# design.net
KiCad netlist of a schematic drawn in Altium Designer
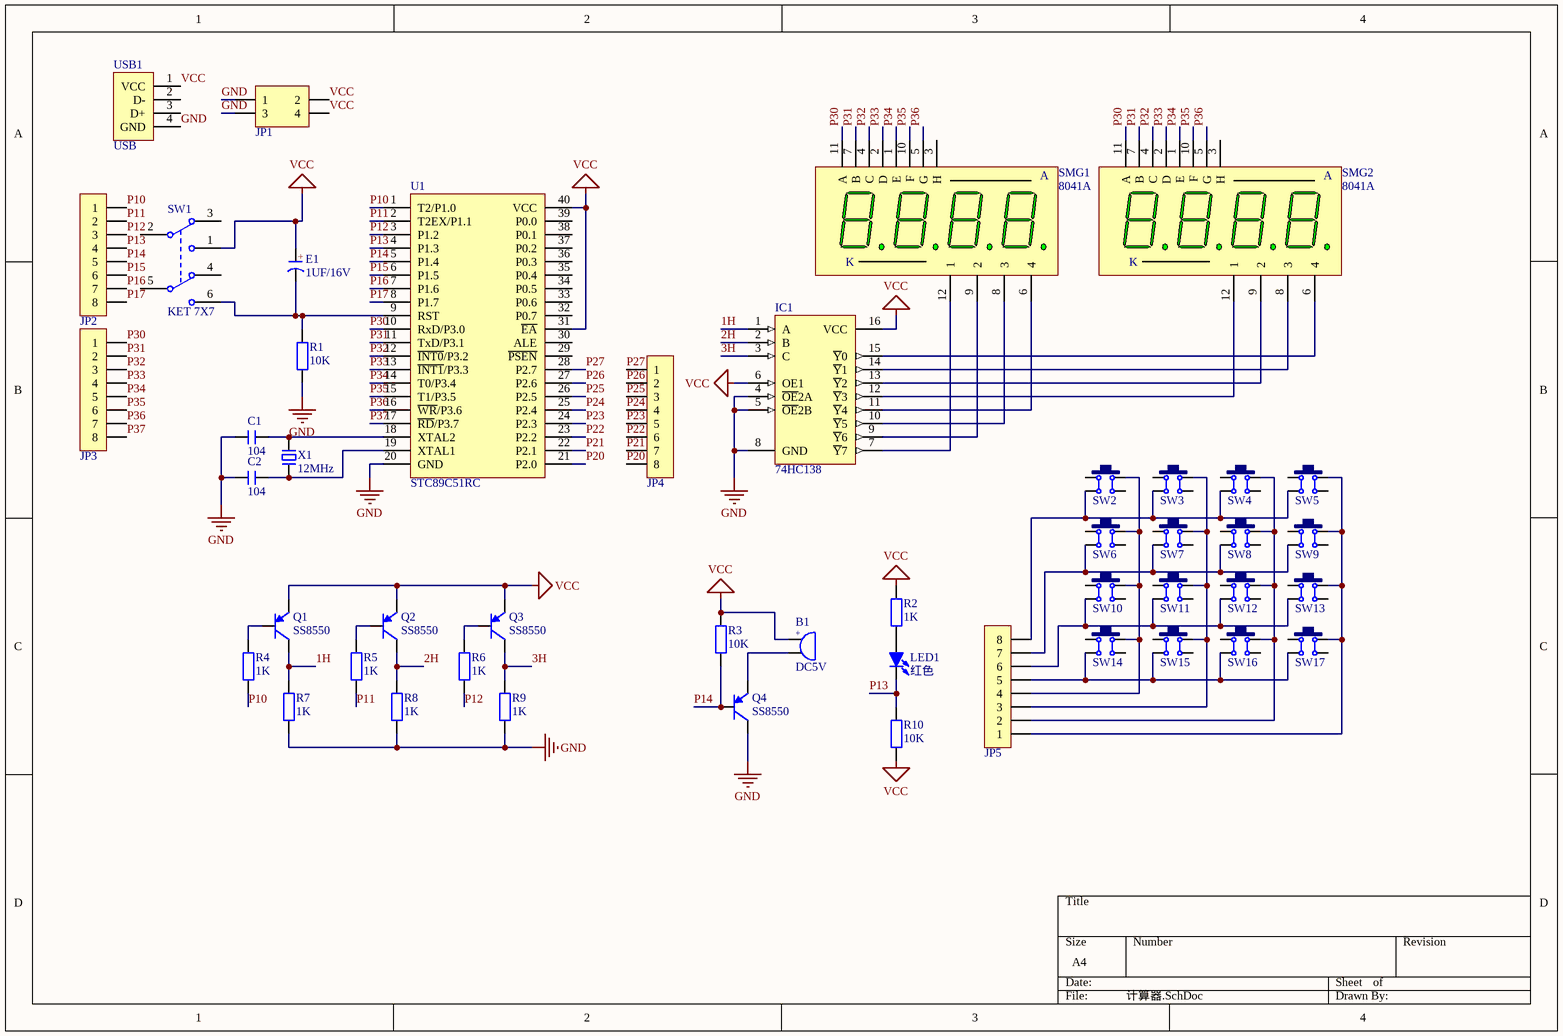
[diagram p0: 计算器.SchDoc]

(export (version "E")
  (design (tool "Eeschema 10.0.6"))
  (components
    (comp (ref "B1")
      (value "DC5V")
      (footprint "BEEP 5x9x5.5")
      (description "蜂鸣器")
      (fields (field (name "版权归属") "黎明电子style"))
      (libsource (lib "未分类器件") (part "BEEP"))
    )
    (comp (ref "C1")
      (value "104")
      (footprint "CC 1.8*3.6")
      (description "直插瓷片电容")
      (fields (field (name "版权归属") "黎明电子style"))
      (libsource (lib "电阻-电容-电感") (part "C-CC"))
    )
    (comp (ref "C2")
      (value "104")
      (footprint "CC 1.8*3.6")
      (description "直插瓷片电容")
      (fields (field (name "版权归属") "黎明电子style"))
      (libsource (lib "电阻-电容-电感") (part "C-CC"))
    )
    (comp (ref "E1")
      (value "1UF/16V")
      (footprint "CAP 1.5*4*8")
      (description "直插电解电容")
      (fields (field (name "版权归属") "黎明电子style"))
      (libsource (lib "电阻-电容-电感") (part "C-CAP"))
    )
    (comp (ref "IC1")
      (value "74HC138")
      (footprint "DIP16-300")
      (description "138译码器")
      (fields (field (name "版权归属") "黎明电子style"))
      (libsource (lib "74系列芯片") (part "74HC138"))
    )
    (comp (ref "JP1")
      (value "Header2X2")
      (footprint "HDR-2X2")
      (description "2*2P接插件")
      (fields (field (name "版权归属") "黎明电子style"))
      (libsource (lib "接插件") (part "Header 2X2"))
    )
    (comp (ref "JP2")
      (value "HDR-1X8")
      (footprint "HDR-1X8")
      (description "8P接插件")
      (fields (field (name "版权归属") "黎明电子style"))
      (libsource (lib "接插件") (part "Header 8"))
    )
    (comp (ref "JP3")
      (value "HDR-1X8")
      (footprint "HDR-1X8")
      (description "8P接插件")
      (fields (field (name "版权归属") "黎明电子style"))
      (libsource (lib "接插件") (part "Header 8"))
    )
    (comp (ref "JP4")
      (value "HDR-1X8")
      (footprint "HDR-1X8")
      (description "8P接插件")
      (fields (field (name "版权归属") "黎明电子style"))
      (libsource (lib "") (part "Header 8_1"))
    )
    (comp (ref "JP5")
      (value "HDR-1X8")
      (footprint "HDR-1X8")
      (description "8P接插件")
      (fields (field (name "版权归属") "黎明电子style"))
      (libsource (lib "") (part "Header 8_2"))
    )
    (comp (ref "LED1")
      (value "红色")
      (footprint "LED 5MM-B")
      (description "5mm插件LED")
      (fields (field (name "版权归属") "黎明电子style"))
      (libsource (lib "LED") (part "LED-5MM"))
    )
    (comp (ref "Q1")
      (value "SS8550")
      (footprint "TO92A")
      (description "高频放大-PNP型")
      (fields (field (name "版权归属") "黎明电子style"))
      (libsource (lib "三极管") (part "8550-DIP"))
    )
    (comp (ref "Q2")
      (value "SS8550")
      (footprint "TO92A")
      (description "高频放大-PNP型")
      (fields (field (name "版权归属") "黎明电子style"))
      (libsource (lib "三极管") (part "8550-DIP"))
    )
    (comp (ref "Q3")
      (value "SS8550")
      (footprint "TO92A")
      (description "高频放大-PNP型")
      (fields (field (name "版权归属") "黎明电子style"))
      (libsource (lib "三极管") (part "8550-DIP"))
    )
    (comp (ref "Q4")
      (value "SS8550")
      (footprint "TO92A")
      (description "高频放大-PNP型")
      (fields (field (name "版权归属") "黎明电子style"))
      (libsource (lib "三极管") (part "8550-DIP"))
    )
    (comp (ref "R1")
      (value "10K")
      (footprint "RS 1/4W")
      (description "直插色环电阻")
      (fields (field (name "版权归属") "黎明电子style"))
      (libsource (lib "电阻-电容-电感") (part "R-CRR"))
    )
    (comp (ref "R2")
      (value "1K")
      (footprint "RS 1/4W")
      (description "直插色环电阻")
      (fields (field (name "版权归属") "黎明电子style"))
      (libsource (lib "电阻-电容-电感") (part "R-CRR"))
    )
    (comp (ref "R3")
      (value "10K")
      (footprint "RS 1/4W")
      (description "直插色环电阻")
      (fields (field (name "版权归属") "黎明电子style"))
      (libsource (lib "电阻-电容-电感") (part "R-CRR"))
    )
    (comp (ref "R4")
      (value "1K")
      (footprint "RS 1/4W")
      (description "直插色环电阻")
      (fields (field (name "版权归属") "黎明电子style"))
      (libsource (lib "电阻-电容-电感") (part "R-CRR"))
    )
    (comp (ref "R5")
      (value "1K")
      (footprint "RS 1/4W")
      (description "直插色环电阻")
      (fields (field (name "版权归属") "黎明电子style"))
      (libsource (lib "电阻-电容-电感") (part "R-CRR"))
    )
    (comp (ref "R6")
      (value "1K")
      (footprint "RS 1/4W")
      (description "直插色环电阻")
      (fields (field (name "版权归属") "黎明电子style"))
      (libsource (lib "电阻-电容-电感") (part "R-CRR"))
    )
    (comp (ref "R7")
      (value "1K")
      (footprint "RS 1/4W")
      (description "直插色环电阻")
      (fields (field (name "版权归属") "黎明电子style"))
      (libsource (lib "电阻-电容-电感") (part "R-CRR"))
    )
    (comp (ref "R8")
      (value "1K")
      (footprint "RS 1/4W")
      (description "直插色环电阻")
      (fields (field (name "版权归属") "黎明电子style"))
      (libsource (lib "电阻-电容-电感") (part "R-CRR"))
    )
    (comp (ref "R9")
      (value "1K")
      (footprint "RS 1/4W")
      (description "直插色环电阻")
      (fields (field (name "版权归属") "黎明电子style"))
      (libsource (lib "电阻-电容-电感") (part "R-CRR"))
    )
    (comp (ref "R10")
      (value "10K")
      (footprint "RS 1/4W")
      (description "直插色环电阻")
      (fields (field (name "版权归属") "黎明电子style"))
      (libsource (lib "电阻-电容-电感") (part "R-CRR"))
    )
    (comp (ref "SMG1")
      (value "8041A")
      (footprint "SMG 0.8-4P")
      (description "0.8寸4位共阴数码管")
      (fields (field (name "版权归属") "黎明电子style"))
      (libsource (lib "显示器件") (part "8041A"))
    )
    (comp (ref "SMG2")
      (value "8041A")
      (footprint "SMG 0.8-4P")
      (description "0.8寸4位共阴数码管")
      (fields (field (name "版权归属") "黎明电子style"))
      (libsource (lib "显示器件") (part "8041A"))
    )
    (comp (ref "SW1")
      (value "KET 7X7")
      (footprint "KFT DIP-7X7")
      (description "7*7自锁开关")
      (fields (field (name "版权归属") "黎明电子style"))
      (libsource (lib "按键-开关") (part "KET 7X7"))
    )
    (comp (ref "SW2")
      (value "6x6x5")
      (footprint "TSW DIP-6*6*6")
      (description "直插6x6轻触开关")
      (fields (field (name "版权归属") "黎明电子style"))
      (libsource (lib "按键-开关") (part "TSW DIP-6x6"))
    )
    (comp (ref "SW3")
      (value "6x6x5")
      (footprint "TSW DIP-6*6*6")
      (description "直插6x6轻触开关")
      (fields (field (name "版权归属") "黎明电子style"))
      (libsource (lib "按键-开关") (part "TSW DIP-6x6"))
    )
    (comp (ref "SW4")
      (value "6x6x5")
      (footprint "TSW DIP-6*6*6")
      (description "直插6x6轻触开关")
      (fields (field (name "版权归属") "黎明电子style"))
      (libsource (lib "按键-开关") (part "TSW DIP-6x6"))
    )
    (comp (ref "SW5")
      (value "6x6x5")
      (footprint "TSW DIP-6*6*6")
      (description "直插6x6轻触开关")
      (fields (field (name "版权归属") "黎明电子style"))
      (libsource (lib "按键-开关") (part "TSW DIP-6x6"))
    )
    (comp (ref "SW6")
      (value "6x6x5")
      (footprint "TSW DIP-6*6*6")
      (description "直插6x6轻触开关")
      (fields (field (name "版权归属") "黎明电子style"))
      (libsource (lib "按键-开关") (part "TSW DIP-6x6"))
    )
    (comp (ref "SW7")
      (value "6x6x5")
      (footprint "TSW DIP-6*6*6")
      (description "直插6x6轻触开关")
      (fields (field (name "版权归属") "黎明电子style"))
      (libsource (lib "按键-开关") (part "TSW DIP-6x6"))
    )
    (comp (ref "SW8")
      (value "6x6x5")
      (footprint "TSW DIP-6*6*6")
      (description "直插6x6轻触开关")
      (fields (field (name "版权归属") "黎明电子style"))
      (libsource (lib "按键-开关") (part "TSW DIP-6x6"))
    )
    (comp (ref "SW9")
      (value "6x6x5")
      (footprint "TSW DIP-6*6*6")
      (description "直插6x6轻触开关")
      (fields (field (name "版权归属") "黎明电子style"))
      (libsource (lib "按键-开关") (part "TSW DIP-6x6"))
    )
    (comp (ref "SW10")
      (value "6x6x5")
      (footprint "TSW DIP-6*6*6")
      (description "直插6x6轻触开关")
      (fields (field (name "版权归属") "黎明电子style"))
      (libsource (lib "按键-开关") (part "TSW DIP-6x6"))
    )
    (comp (ref "SW11")
      (value "6x6x5")
      (footprint "TSW DIP-6*6*6")
      (description "直插6x6轻触开关")
      (fields (field (name "版权归属") "黎明电子style"))
      (libsource (lib "按键-开关") (part "TSW DIP-6x6"))
    )
    (comp (ref "SW12")
      (value "6x6x5")
      (footprint "TSW DIP-6*6*6")
      (description "直插6x6轻触开关")
      (fields (field (name "版权归属") "黎明电子style"))
      (libsource (lib "按键-开关") (part "TSW DIP-6x6"))
    )
    (comp (ref "SW13")
      (value "6x6x5")
      (footprint "TSW DIP-6*6*6")
      (description "直插6x6轻触开关")
      (fields (field (name "版权归属") "黎明电子style"))
      (libsource (lib "按键-开关") (part "TSW DIP-6x6"))
    )
    (comp (ref "SW14")
      (value "6x6x5")
      (footprint "TSW DIP-6*6*6")
      (description "直插6x6轻触开关")
      (fields (field (name "版权归属") "黎明电子style"))
      (libsource (lib "按键-开关") (part "TSW DIP-6x6"))
    )
    (comp (ref "SW15")
      (value "6x6x5")
      (footprint "TSW DIP-6*6*6")
      (description "直插6x6轻触开关")
      (fields (field (name "版权归属") "黎明电子style"))
      (libsource (lib "按键-开关") (part "TSW DIP-6x6"))
    )
    (comp (ref "SW16")
      (value "6x6x5")
      (footprint "TSW DIP-6*6*6")
      (description "直插6x6轻触开关")
      (fields (field (name "版权归属") "黎明电子style"))
      (libsource (lib "按键-开关") (part "TSW DIP-6x6"))
    )
    (comp (ref "SW17")
      (value "6x6x5")
      (footprint "TSW DIP-6*6*6")
      (description "直插6x6轻触开关")
      (fields (field (name "版权归属") "黎明电子style"))
      (libsource (lib "按键-开关") (part "TSW DIP-6x6"))
    )
    (comp (ref "U1")
      (value "STC89C51RC")
      (footprint "DIP40-600")
      (description "STC单片机")
      (fields (field (name "版权归属") "黎明电子style"))
      (libsource (lib "STC系列单片机") (part "STC89C51RC"))
    )
    (comp (ref "USB1")
      (value "USB")
      (footprint "USB-A/S_A")
      (description "USB-A型母接口")
      (fields (field (name "版权归属") "黎明电子style"))
      (libsource (lib "接口类") (part "USB-A/S"))
    )
    (comp (ref "X1")
      (value "12MHz")
      (footprint "XTAL-3X10")
      (description "2脚晶振")
      (fields (field (name "版权归属") "黎明电子style"))
      (libsource (lib "保险丝-晶振") (part "XTAL-2"))
    )
  )
  (nets
    (net (code "1") (name "/1H") (class "Default")
      (node (ref "IC1") (pin "1") (pinfunction "A_1") (pintype "input"))
      (node (ref "Q1") (pin "3") (pinfunction "C_3") (pintype "passive"))
      (node (ref "R7") (pin "2") (pinfunction "2_2") (pintype "passive"))
    )
    (net (code "2") (name "/2H") (class "Default")
      (node (ref "IC1") (pin "2") (pinfunction "B_2") (pintype "input"))
      (node (ref "Q2") (pin "3") (pinfunction "C_3") (pintype "passive"))
      (node (ref "R8") (pin "2") (pinfunction "2_2") (pintype "passive"))
    )
    (net (code "3") (name "/3H") (class "Default")
      (node (ref "IC1") (pin "3") (pinfunction "C_3") (pintype "input"))
      (node (ref "Q3") (pin "3") (pinfunction "C_3") (pintype "passive"))
      (node (ref "R9") (pin "2") (pinfunction "2_2") (pintype "passive"))
    )
    (net (code "4") (name "/P10") (class "Default")
      (node (ref "JP2") (pin "1") (pinfunction "1_1") (pintype "passive"))
      (node (ref "R4") (pin "1") (pinfunction "1_1") (pintype "passive"))
      (node (ref "U1") (pin "1") (pinfunction "T2/P1.0_1") (pintype "passive"))
    )
    (net (code "5") (name "/P11") (class "Default")
      (node (ref "JP2") (pin "2") (pinfunction "2_2") (pintype "passive"))
      (node (ref "R5") (pin "1") (pinfunction "1_1") (pintype "passive"))
      (node (ref "U1") (pin "2") (pinfunction "T2EX/P1.1_2") (pintype "passive"))
    )
    (net (code "6") (name "/P12") (class "Default")
      (node (ref "JP2") (pin "3") (pinfunction "3_3") (pintype "passive"))
      (node (ref "R6") (pin "1") (pinfunction "1_1") (pintype "passive"))
      (node (ref "U1") (pin "3") (pinfunction "P1.2_3") (pintype "passive"))
    )
    (net (code "7") (name "/P13") (class "Default")
      (node (ref "JP2") (pin "4") (pinfunction "4_4") (pintype "passive"))
      (node (ref "LED1") (pin "2") (pinfunction "K_2") (pintype "passive"))
      (node (ref "R10") (pin "2") (pinfunction "2_2") (pintype "passive"))
      (node (ref "U1") (pin "4") (pinfunction "P1.3_4") (pintype "passive"))
    )
    (net (code "8") (name "/P14") (class "Default")
      (node (ref "JP2") (pin "5") (pinfunction "5_5") (pintype "passive"))
      (node (ref "Q4") (pin "2") (pinfunction "B_2") (pintype "passive"))
      (node (ref "R3") (pin "1") (pinfunction "1_1") (pintype "passive"))
      (node (ref "U1") (pin "5") (pinfunction "P1.4_5") (pintype "passive"))
    )
    (net (code "9") (name "/P15") (class "Default")
      (node (ref "JP2") (pin "6") (pinfunction "6_6") (pintype "passive"))
      (node (ref "U1") (pin "6") (pinfunction "P1.5_6") (pintype "passive"))
    )
    (net (code "10") (name "/P16") (class "Default")
      (node (ref "JP2") (pin "7") (pinfunction "7_7") (pintype "passive"))
      (node (ref "U1") (pin "7") (pinfunction "P1.6_7") (pintype "passive"))
    )
    (net (code "11") (name "/P17") (class "Default")
      (node (ref "JP2") (pin "8") (pinfunction "8_8") (pintype "passive"))
      (node (ref "U1") (pin "8") (pinfunction "P1.7_8") (pintype "passive"))
    )
    (net (code "12") (name "/P20") (class "Default")
      (node (ref "JP4") (pin "8") (pinfunction "8_8") (pintype "passive"))
      (node (ref "U1") (pin "21") (pinfunction "P2.0_21") (pintype "passive"))
    )
    (net (code "13") (name "/P21") (class "Default")
      (node (ref "JP4") (pin "7") (pinfunction "7_7") (pintype "passive"))
      (node (ref "U1") (pin "22") (pinfunction "P2.1_22") (pintype "passive"))
    )
    (net (code "14") (name "/P22") (class "Default")
      (node (ref "JP4") (pin "6") (pinfunction "6_6") (pintype "passive"))
      (node (ref "U1") (pin "23") (pinfunction "P2.2_23") (pintype "passive"))
    )
    (net (code "15") (name "/P23") (class "Default")
      (node (ref "JP4") (pin "5") (pinfunction "5_5") (pintype "passive"))
      (node (ref "U1") (pin "24") (pinfunction "P2.3_24") (pintype "passive"))
    )
    (net (code "16") (name "/P24") (class "Default")
      (node (ref "JP4") (pin "4") (pinfunction "4_4") (pintype "passive"))
      (node (ref "U1") (pin "25") (pinfunction "P2.4_25") (pintype "passive"))
    )
    (net (code "17") (name "/P25") (class "Default")
      (node (ref "JP4") (pin "3") (pinfunction "3_3") (pintype "passive"))
      (node (ref "U1") (pin "26") (pinfunction "P2.5_26") (pintype "passive"))
    )
    (net (code "18") (name "/P26") (class "Default")
      (node (ref "JP4") (pin "2") (pinfunction "2_2") (pintype "passive"))
      (node (ref "U1") (pin "27") (pinfunction "P2.6_27") (pintype "passive"))
    )
    (net (code "19") (name "/P27") (class "Default")
      (node (ref "JP4") (pin "1") (pinfunction "1_1") (pintype "passive"))
      (node (ref "U1") (pin "28") (pinfunction "P2.7_28") (pintype "passive"))
    )
    (net (code "20") (name "/P30") (class "Default")
      (node (ref "JP3") (pin "1") (pinfunction "1_1") (pintype "passive"))
      (node (ref "SMG1") (pin "11") (pinfunction "A_11") (pintype "passive"))
      (node (ref "SMG2") (pin "11") (pinfunction "A_11") (pintype "passive"))
      (node (ref "U1") (pin "10") (pinfunction "RxD/P3.0_10") (pintype "passive"))
    )
    (net (code "21") (name "/P31") (class "Default")
      (node (ref "JP3") (pin "2") (pinfunction "2_2") (pintype "passive"))
      (node (ref "SMG1") (pin "7") (pinfunction "B_7") (pintype "passive"))
      (node (ref "SMG2") (pin "7") (pinfunction "B_7") (pintype "passive"))
      (node (ref "U1") (pin "11") (pinfunction "TxD/P3.1_11") (pintype "passive"))
    )
    (net (code "22") (name "/P32") (class "Default")
      (node (ref "JP3") (pin "3") (pinfunction "3_3") (pintype "passive"))
      (node (ref "SMG1") (pin "4") (pinfunction "C_4") (pintype "passive"))
      (node (ref "SMG2") (pin "4") (pinfunction "C_4") (pintype "passive"))
      (node (ref "U1") (pin "12") (pinfunction "~{INT0}/P3.2_12") (pintype "passive"))
    )
    (net (code "23") (name "/P33") (class "Default")
      (node (ref "JP3") (pin "4") (pinfunction "4_4") (pintype "passive"))
      (node (ref "SMG1") (pin "2") (pinfunction "D_2") (pintype "passive"))
      (node (ref "SMG2") (pin "2") (pinfunction "D_2") (pintype "passive"))
      (node (ref "U1") (pin "13") (pinfunction "~{INT1}/P3.3_13") (pintype "passive"))
    )
    (net (code "24") (name "/P34") (class "Default")
      (node (ref "JP3") (pin "5") (pinfunction "5_5") (pintype "passive"))
      (node (ref "SMG1") (pin "1") (pinfunction "E_1") (pintype "passive"))
      (node (ref "SMG2") (pin "1") (pinfunction "E_1") (pintype "passive"))
      (node (ref "U1") (pin "14") (pinfunction "T0/P3.4_14") (pintype "passive"))
    )
    (net (code "25") (name "/P35") (class "Default")
      (node (ref "JP3") (pin "6") (pinfunction "6_6") (pintype "passive"))
      (node (ref "SMG1") (pin "10") (pinfunction "F_10") (pintype "passive"))
      (node (ref "SMG2") (pin "10") (pinfunction "F_10") (pintype "passive"))
      (node (ref "U1") (pin "15") (pinfunction "T1/P3.5_15") (pintype "passive"))
    )
    (net (code "26") (name "/P36") (class "Default")
      (node (ref "JP3") (pin "7") (pinfunction "7_7") (pintype "passive"))
      (node (ref "SMG1") (pin "5") (pinfunction "G_5") (pintype "passive"))
      (node (ref "SMG2") (pin "5") (pinfunction "G_5") (pintype "passive"))
      (node (ref "U1") (pin "16") (pinfunction "~{WR}/P3.6_16") (pintype "passive"))
    )
    (net (code "27") (name "/P37") (class "Default")
      (node (ref "JP3") (pin "8") (pinfunction "8_8") (pintype "passive"))
      (node (ref "U1") (pin "17") (pinfunction "~{RD}/P3.7_17") (pintype "passive"))
    )
    (net (code "28") (name "GND") (class "Default")
      (node (ref "C1") (pin "1") (pinfunction "1_1") (pintype "passive"))
      (node (ref "C2") (pin "1") (pinfunction "1_1") (pintype "passive"))
      (node (ref "IC1") (pin "4") (pinfunction "~{OE}2A_4") (pintype "input"))
      (node (ref "IC1") (pin "5") (pinfunction "~{OE}2B_5") (pintype "input"))
      (node (ref "IC1") (pin "8") (pinfunction "GND_8") (pintype "power_in"))
      (node (ref "JP1") (pin "1") (pinfunction "1_1") (pintype "passive"))
      (node (ref "JP1") (pin "3") (pinfunction "3_3") (pintype "passive"))
      (node (ref "Q4") (pin "3") (pinfunction "C_3") (pintype "passive"))
      (node (ref "R1") (pin "1") (pinfunction "1_1") (pintype "passive"))
      (node (ref "R7") (pin "1") (pinfunction "1_1") (pintype "passive"))
      (node (ref "R8") (pin "1") (pinfunction "1_1") (pintype "passive"))
      (node (ref "R9") (pin "1") (pinfunction "1_1") (pintype "passive"))
      (node (ref "U1") (pin "20") (pinfunction "GND_20") (pintype "passive"))
      (node (ref "USB1") (pin "4") (pinfunction "GND_4") (pintype "passive"))
    )
    (net (code "29") (name "Net-(E1-K)") (class "Default")
      (node (ref "E1") (pin "2") (pinfunction "K_2") (pintype "passive"))
      (node (ref "R1") (pin "2") (pinfunction "2_2") (pintype "passive"))
      (node (ref "SW1") (pin "6") (pinfunction "NC2_6") (pintype "passive"))
      (node (ref "U1") (pin "9") (pinfunction "RST_9") (pintype "passive"))
    )
    (net (code "30") (name "Net-(IC1-~{Y}0)") (class "Default")
      (node (ref "IC1") (pin "15") (pinfunction "~{Y}0_15") (pintype "output"))
      (node (ref "SMG2") (pin "6") (pinfunction "4_6") (pintype "passive"))
    )
    (net (code "31") (name "Net-(IC1-~{Y}1)") (class "Default")
      (node (ref "IC1") (pin "14") (pinfunction "~{Y}1_14") (pintype "output"))
      (node (ref "SMG2") (pin "8") (pinfunction "3_8") (pintype "passive"))
    )
    (net (code "32") (name "Net-(IC1-~{Y}2)") (class "Default")
      (node (ref "IC1") (pin "13") (pinfunction "~{Y}2_13") (pintype "output"))
      (node (ref "SMG2") (pin "9") (pinfunction "2_9") (pintype "passive"))
    )
    (net (code "33") (name "Net-(IC1-~{Y}3)") (class "Default")
      (node (ref "IC1") (pin "12") (pinfunction "~{Y}3_12") (pintype "output"))
      (node (ref "SMG2") (pin "12") (pinfunction "1_12") (pintype "passive"))
    )
    (net (code "34") (name "Net-(IC1-~{Y}4)") (class "Default")
      (node (ref "IC1") (pin "11") (pinfunction "~{Y}4_11") (pintype "output"))
      (node (ref "SMG1") (pin "6") (pinfunction "4_6") (pintype "passive"))
    )
    (net (code "35") (name "Net-(IC1-~{Y}5)") (class "Default")
      (node (ref "IC1") (pin "10") (pinfunction "~{Y}5_10") (pintype "output"))
      (node (ref "SMG1") (pin "8") (pinfunction "3_8") (pintype "passive"))
    )
    (net (code "36") (name "Net-(IC1-~{Y}6)") (class "Default")
      (node (ref "IC1") (pin "9") (pinfunction "~{Y}6_9") (pintype "output"))
      (node (ref "SMG1") (pin "9") (pinfunction "2_9") (pintype "passive"))
    )
    (net (code "37") (name "Net-(IC1-~{Y}7)") (class "Default")
      (node (ref "IC1") (pin "7") (pinfunction "~{Y}7_7") (pintype "output"))
      (node (ref "SMG1") (pin "12") (pinfunction "1_12") (pintype "passive"))
    )
    (net (code "38") (name "Net-(JP5-Pad1)") (class "Default")
      (node (ref "JP5") (pin "1") (pinfunction "1_1") (pintype "passive"))
      (node (ref "SW13") (pin "2") (pinfunction "2_2") (pintype "passive"))
      (node (ref "SW17") (pin "2") (pinfunction "2_2") (pintype "passive"))
      (node (ref "SW5") (pin "2") (pinfunction "2_2") (pintype "passive"))
      (node (ref "SW9") (pin "2") (pinfunction "2_2") (pintype "passive"))
    )
    (net (code "39") (name "Net-(JP5-Pad2)") (class "Default")
      (node (ref "JP5") (pin "2") (pinfunction "2_2") (pintype "passive"))
      (node (ref "SW12") (pin "2") (pinfunction "2_2") (pintype "passive"))
      (node (ref "SW16") (pin "2") (pinfunction "2_2") (pintype "passive"))
      (node (ref "SW4") (pin "2") (pinfunction "2_2") (pintype "passive"))
      (node (ref "SW8") (pin "2") (pinfunction "2_2") (pintype "passive"))
    )
    (net (code "40") (name "Net-(JP5-Pad3)") (class "Default")
      (node (ref "JP5") (pin "3") (pinfunction "3_3") (pintype "passive"))
      (node (ref "SW11") (pin "2") (pinfunction "2_2") (pintype "passive"))
      (node (ref "SW15") (pin "2") (pinfunction "2_2") (pintype "passive"))
      (node (ref "SW3") (pin "2") (pinfunction "2_2") (pintype "passive"))
      (node (ref "SW7") (pin "2") (pinfunction "2_2") (pintype "passive"))
    )
    (net (code "41") (name "Net-(JP5-Pad4)") (class "Default")
      (node (ref "JP5") (pin "4") (pinfunction "4_4") (pintype "passive"))
      (node (ref "SW10") (pin "2") (pinfunction "2_2") (pintype "passive"))
      (node (ref "SW14") (pin "2") (pinfunction "2_2") (pintype "passive"))
      (node (ref "SW2") (pin "2") (pinfunction "2_2") (pintype "passive"))
      (node (ref "SW6") (pin "2") (pinfunction "2_2") (pintype "passive"))
    )
    (net (code "42") (name "Net-(JP5-Pad5)") (class "Default")
      (node (ref "JP5") (pin "5") (pinfunction "5_5") (pintype "passive"))
      (node (ref "SW14") (pin "4") (pinfunction "4_4") (pintype "passive"))
      (node (ref "SW15") (pin "4") (pinfunction "4_4") (pintype "passive"))
      (node (ref "SW16") (pin "4") (pinfunction "4_4") (pintype "passive"))
      (node (ref "SW17") (pin "4") (pinfunction "4_4") (pintype "passive"))
    )
    (net (code "43") (name "Net-(JP5-Pad6)") (class "Default")
      (node (ref "JP5") (pin "6") (pinfunction "6_6") (pintype "passive"))
      (node (ref "SW10") (pin "4") (pinfunction "4_4") (pintype "passive"))
      (node (ref "SW11") (pin "4") (pinfunction "4_4") (pintype "passive"))
      (node (ref "SW12") (pin "4") (pinfunction "4_4") (pintype "passive"))
      (node (ref "SW13") (pin "4") (pinfunction "4_4") (pintype "passive"))
    )
    (net (code "44") (name "Net-(JP5-Pad7)") (class "Default")
      (node (ref "JP5") (pin "7") (pinfunction "7_7") (pintype "passive"))
      (node (ref "SW6") (pin "4") (pinfunction "4_4") (pintype "passive"))
      (node (ref "SW7") (pin "4") (pinfunction "4_4") (pintype "passive"))
      (node (ref "SW8") (pin "4") (pinfunction "4_4") (pintype "passive"))
      (node (ref "SW9") (pin "4") (pinfunction "4_4") (pintype "passive"))
    )
    (net (code "45") (name "Net-(JP5-Pad8)") (class "Default")
      (node (ref "JP5") (pin "8") (pinfunction "8_8") (pintype "passive"))
      (node (ref "SW2") (pin "4") (pinfunction "4_4") (pintype "passive"))
      (node (ref "SW3") (pin "4") (pinfunction "4_4") (pintype "passive"))
      (node (ref "SW4") (pin "4") (pinfunction "4_4") (pintype "passive"))
      (node (ref "SW5") (pin "4") (pinfunction "4_4") (pintype "passive"))
    )
    (net (code "46") (name "Net-(LED1-A)") (class "Default")
      (node (ref "LED1") (pin "1") (pinfunction "A_1") (pintype "passive"))
      (node (ref "R2") (pin "1") (pinfunction "1_1") (pintype "passive"))
    )
    (net (code "47") (name "Net-(Q1-B)") (class "Default")
      (node (ref "Q1") (pin "2") (pinfunction "B_2") (pintype "passive"))
      (node (ref "R4") (pin "2") (pinfunction "2_2") (pintype "passive"))
    )
    (net (code "48") (name "Net-(Q2-B)") (class "Default")
      (node (ref "Q2") (pin "2") (pinfunction "B_2") (pintype "passive"))
      (node (ref "R5") (pin "2") (pinfunction "2_2") (pintype "passive"))
    )
    (net (code "49") (name "Net-(Q3-B)") (class "Default")
      (node (ref "Q3") (pin "2") (pinfunction "B_2") (pintype "passive"))
      (node (ref "R6") (pin "2") (pinfunction "2_2") (pintype "passive"))
    )
    (net (code "50") (name "Net-(Q4-E)") (class "Default")
      (node (ref "B1") (pin "2") (pinfunction "2_2") (pintype "passive"))
      (node (ref "Q4") (pin "1") (pinfunction "E_1") (pintype "passive"))
    )
    (net (code "51") (name "Net-(U1-XTAL1)") (class "Default")
      (node (ref "C2") (pin "2") (pinfunction "2_2") (pintype "passive"))
      (node (ref "U1") (pin "19") (pinfunction "XTAL1_19") (pintype "passive"))
      (node (ref "X1") (pin "1") (pinfunction "1_1") (pintype "passive"))
    )
    (net (code "52") (name "Net-(U1-XTAL2)") (class "Default")
      (node (ref "C1") (pin "2") (pinfunction "2_2") (pintype "passive"))
      (node (ref "U1") (pin "18") (pinfunction "XTAL2_18") (pintype "passive"))
      (node (ref "X1") (pin "2") (pinfunction "2_2") (pintype "passive"))
    )
    (net (code "53") (name "VCC") (class "Default")
      (node (ref "B1") (pin "1") (pinfunction "1_1") (pintype "passive"))
      (node (ref "E1") (pin "1") (pinfunction "A_1") (pintype "passive"))
      (node (ref "IC1") (pin "16") (pinfunction "VCC_16") (pintype "power_in"))
      (node (ref "IC1") (pin "6") (pinfunction "OE1_6") (pintype "input"))
      (node (ref "JP1") (pin "2") (pinfunction "2_2") (pintype "passive"))
      (node (ref "JP1") (pin "4") (pinfunction "4_4") (pintype "passive"))
      (node (ref "Q1") (pin "1") (pinfunction "E_1") (pintype "passive"))
      (node (ref "Q2") (pin "1") (pinfunction "E_1") (pintype "passive"))
      (node (ref "Q3") (pin "1") (pinfunction "E_1") (pintype "passive"))
      (node (ref "R10") (pin "1") (pinfunction "1_1") (pintype "passive"))
      (node (ref "R2") (pin "2") (pinfunction "2_2") (pintype "passive"))
      (node (ref "R3") (pin "2") (pinfunction "2_2") (pintype "passive"))
      (node (ref "SW1") (pin "1") (pinfunction "NC1_1") (pintype "passive"))
      (node (ref "U1") (pin "31") (pinfunction "~{EA}_31") (pintype "passive"))
      (node (ref "U1") (pin "40") (pinfunction "VCC_40") (pintype "passive"))
      (node (ref "USB1") (pin "1") (pinfunction "VCC_1") (pintype "passive"))
    )
    (net (code "54") (name "unconnected-(SMG1-H-Pad3)") (class "Default")
      (node (ref "SMG1") (pin "3") (pinfunction "H_3") (pintype "passive"))
    )
    (net (code "55") (name "unconnected-(SMG2-H-Pad3)") (class "Default")
      (node (ref "SMG2") (pin "3") (pinfunction "H_3") (pintype "passive"))
    )
    (net (code "56") (name "unconnected-(SW1-COM2-Pad2)") (class "Default")
      (node (ref "SW1") (pin "2") (pinfunction "COM2_2") (pintype "passive"))
    )
    (net (code "57") (name "unconnected-(SW1-COM2-Pad5)") (class "Default")
      (node (ref "SW1") (pin "5") (pinfunction "COM2_5") (pintype "passive"))
    )
    (net (code "58") (name "unconnected-(SW1-NO1-Pad3)") (class "Default")
      (node (ref "SW1") (pin "3") (pinfunction "NO1_3") (pintype "passive"))
    )
    (net (code "59") (name "unconnected-(SW1-NO2-Pad4)") (class "Default")
      (node (ref "SW1") (pin "4") (pinfunction "NO2_4") (pintype "passive"))
    )
    (net (code "60") (name "unconnected-(SW2-Pad1)") (class "Default")
      (node (ref "SW2") (pin "1") (pinfunction "1_1") (pintype "passive"))
    )
    (net (code "61") (name "unconnected-(SW2-Pad3)") (class "Default")
      (node (ref "SW2") (pin "3") (pinfunction "3_3") (pintype "passive"))
    )
    (net (code "62") (name "unconnected-(SW3-Pad1)") (class "Default")
      (node (ref "SW3") (pin "1") (pinfunction "1_1") (pintype "passive"))
    )
    (net (code "63") (name "unconnected-(SW3-Pad3)") (class "Default")
      (node (ref "SW3") (pin "3") (pinfunction "3_3") (pintype "passive"))
    )
    (net (code "64") (name "unconnected-(SW4-Pad1)") (class "Default")
      (node (ref "SW4") (pin "1") (pinfunction "1_1") (pintype "passive"))
    )
    (net (code "65") (name "unconnected-(SW4-Pad3)") (class "Default")
      (node (ref "SW4") (pin "3") (pinfunction "3_3") (pintype "passive"))
    )
    (net (code "66") (name "unconnected-(SW5-Pad1)") (class "Default")
      (node (ref "SW5") (pin "1") (pinfunction "1_1") (pintype "passive"))
    )
    (net (code "67") (name "unconnected-(SW5-Pad3)") (class "Default")
      (node (ref "SW5") (pin "3") (pinfunction "3_3") (pintype "passive"))
    )
    (net (code "68") (name "unconnected-(SW6-Pad1)") (class "Default")
      (node (ref "SW6") (pin "1") (pinfunction "1_1") (pintype "passive"))
    )
    (net (code "69") (name "unconnected-(SW6-Pad3)") (class "Default")
      (node (ref "SW6") (pin "3") (pinfunction "3_3") (pintype "passive"))
    )
    (net (code "70") (name "unconnected-(SW7-Pad1)") (class "Default")
      (node (ref "SW7") (pin "1") (pinfunction "1_1") (pintype "passive"))
    )
    (net (code "71") (name "unconnected-(SW7-Pad3)") (class "Default")
      (node (ref "SW7") (pin "3") (pinfunction "3_3") (pintype "passive"))
    )
    (net (code "72") (name "unconnected-(SW8-Pad1)") (class "Default")
      (node (ref "SW8") (pin "1") (pinfunction "1_1") (pintype "passive"))
    )
    (net (code "73") (name "unconnected-(SW8-Pad3)") (class "Default")
      (node (ref "SW8") (pin "3") (pinfunction "3_3") (pintype "passive"))
    )
    (net (code "74") (name "unconnected-(SW9-Pad1)") (class "Default")
      (node (ref "SW9") (pin "1") (pinfunction "1_1") (pintype "passive"))
    )
    (net (code "75") (name "unconnected-(SW9-Pad3)") (class "Default")
      (node (ref "SW9") (pin "3") (pinfunction "3_3") (pintype "passive"))
    )
    (net (code "76") (name "unconnected-(SW10-Pad1)") (class "Default")
      (node (ref "SW10") (pin "1") (pinfunction "1_1") (pintype "passive"))
    )
    (net (code "77") (name "unconnected-(SW10-Pad3)") (class "Default")
      (node (ref "SW10") (pin "3") (pinfunction "3_3") (pintype "passive"))
    )
    (net (code "78") (name "unconnected-(SW11-Pad1)") (class "Default")
      (node (ref "SW11") (pin "1") (pinfunction "1_1") (pintype "passive"))
    )
    (net (code "79") (name "unconnected-(SW11-Pad3)") (class "Default")
      (node (ref "SW11") (pin "3") (pinfunction "3_3") (pintype "passive"))
    )
    (net (code "80") (name "unconnected-(SW12-Pad1)") (class "Default")
      (node (ref "SW12") (pin "1") (pinfunction "1_1") (pintype "passive"))
    )
    (net (code "81") (name "unconnected-(SW12-Pad3)") (class "Default")
      (node (ref "SW12") (pin "3") (pinfunction "3_3") (pintype "passive"))
    )
    (net (code "82") (name "unconnected-(SW13-Pad1)") (class "Default")
      (node (ref "SW13") (pin "1") (pinfunction "1_1") (pintype "passive"))
    )
    (net (code "83") (name "unconnected-(SW13-Pad3)") (class "Default")
      (node (ref "SW13") (pin "3") (pinfunction "3_3") (pintype "passive"))
    )
    (net (code "84") (name "unconnected-(SW14-Pad1)") (class "Default")
      (node (ref "SW14") (pin "1") (pinfunction "1_1") (pintype "passive"))
    )
    (net (code "85") (name "unconnected-(SW14-Pad3)") (class "Default")
      (node (ref "SW14") (pin "3") (pinfunction "3_3") (pintype "passive"))
    )
    (net (code "86") (name "unconnected-(SW15-Pad1)") (class "Default")
      (node (ref "SW15") (pin "1") (pinfunction "1_1") (pintype "passive"))
    )
    (net (code "87") (name "unconnected-(SW15-Pad3)") (class "Default")
      (node (ref "SW15") (pin "3") (pinfunction "3_3") (pintype "passive"))
    )
    (net (code "88") (name "unconnected-(SW16-Pad1)") (class "Default")
      (node (ref "SW16") (pin "1") (pinfunction "1_1") (pintype "passive"))
    )
    (net (code "89") (name "unconnected-(SW16-Pad3)") (class "Default")
      (node (ref "SW16") (pin "3") (pinfunction "3_3") (pintype "passive"))
    )
    (net (code "90") (name "unconnected-(SW17-Pad1)") (class "Default")
      (node (ref "SW17") (pin "1") (pinfunction "1_1") (pintype "passive"))
    )
    (net (code "91") (name "unconnected-(SW17-Pad3)") (class "Default")
      (node (ref "SW17") (pin "3") (pinfunction "3_3") (pintype "passive"))
    )
    (net (code "92") (name "unconnected-(U1-ALE-Pad30)") (class "Default")
      (node (ref "U1") (pin "30") (pinfunction "ALE_30") (pintype "passive"))
    )
    (net (code "93") (name "unconnected-(U1-P0.0-Pad39)") (class "Default")
      (node (ref "U1") (pin "39") (pinfunction "P0.0_39") (pintype "passive"))
    )
    (net (code "94") (name "unconnected-(U1-P0.1-Pad38)") (class "Default")
      (node (ref "U1") (pin "38") (pinfunction "P0.1_38") (pintype "passive"))
    )
    (net (code "95") (name "unconnected-(U1-P0.2-Pad37)") (class "Default")
      (node (ref "U1") (pin "37") (pinfunction "P0.2_37") (pintype "passive"))
    )
    (net (code "96") (name "unconnected-(U1-P0.3-Pad36)") (class "Default")
      (node (ref "U1") (pin "36") (pinfunction "P0.3_36") (pintype "passive"))
    )
    (net (code "97") (name "unconnected-(U1-P0.4-Pad35)") (class "Default")
      (node (ref "U1") (pin "35") (pinfunction "P0.4_35") (pintype "passive"))
    )
    (net (code "98") (name "unconnected-(U1-P0.5-Pad34)") (class "Default")
      (node (ref "U1") (pin "34") (pinfunction "P0.5_34") (pintype "passive"))
    )
    (net (code "99") (name "unconnected-(U1-P0.6-Pad33)") (class "Default")
      (node (ref "U1") (pin "33") (pinfunction "P0.6_33") (pintype "passive"))
    )
    (net (code "100") (name "unconnected-(U1-P0.7-Pad32)") (class "Default")
      (node (ref "U1") (pin "32") (pinfunction "P0.7_32") (pintype "passive"))
    )
    (net (code "101") (name "unconnected-(U1-~{PSEN}-Pad29)") (class "Default")
      (node (ref "U1") (pin "29") (pinfunction "~{PSEN}_29") (pintype "passive"))
    )
    (net (code "102") (name "unconnected-(USB1-D+-Pad3)") (class "Default")
      (node (ref "USB1") (pin "3") (pinfunction "D+_3") (pintype "passive"))
    )
    (net (code "103") (name "unconnected-(USB1-D--Pad2)") (class "Default")
      (node (ref "USB1") (pin "2") (pinfunction "D-_2") (pintype "passive"))
    )
  )
)
